# con-left.net
KiCad netlist of a schematic drawn in Altium Designer
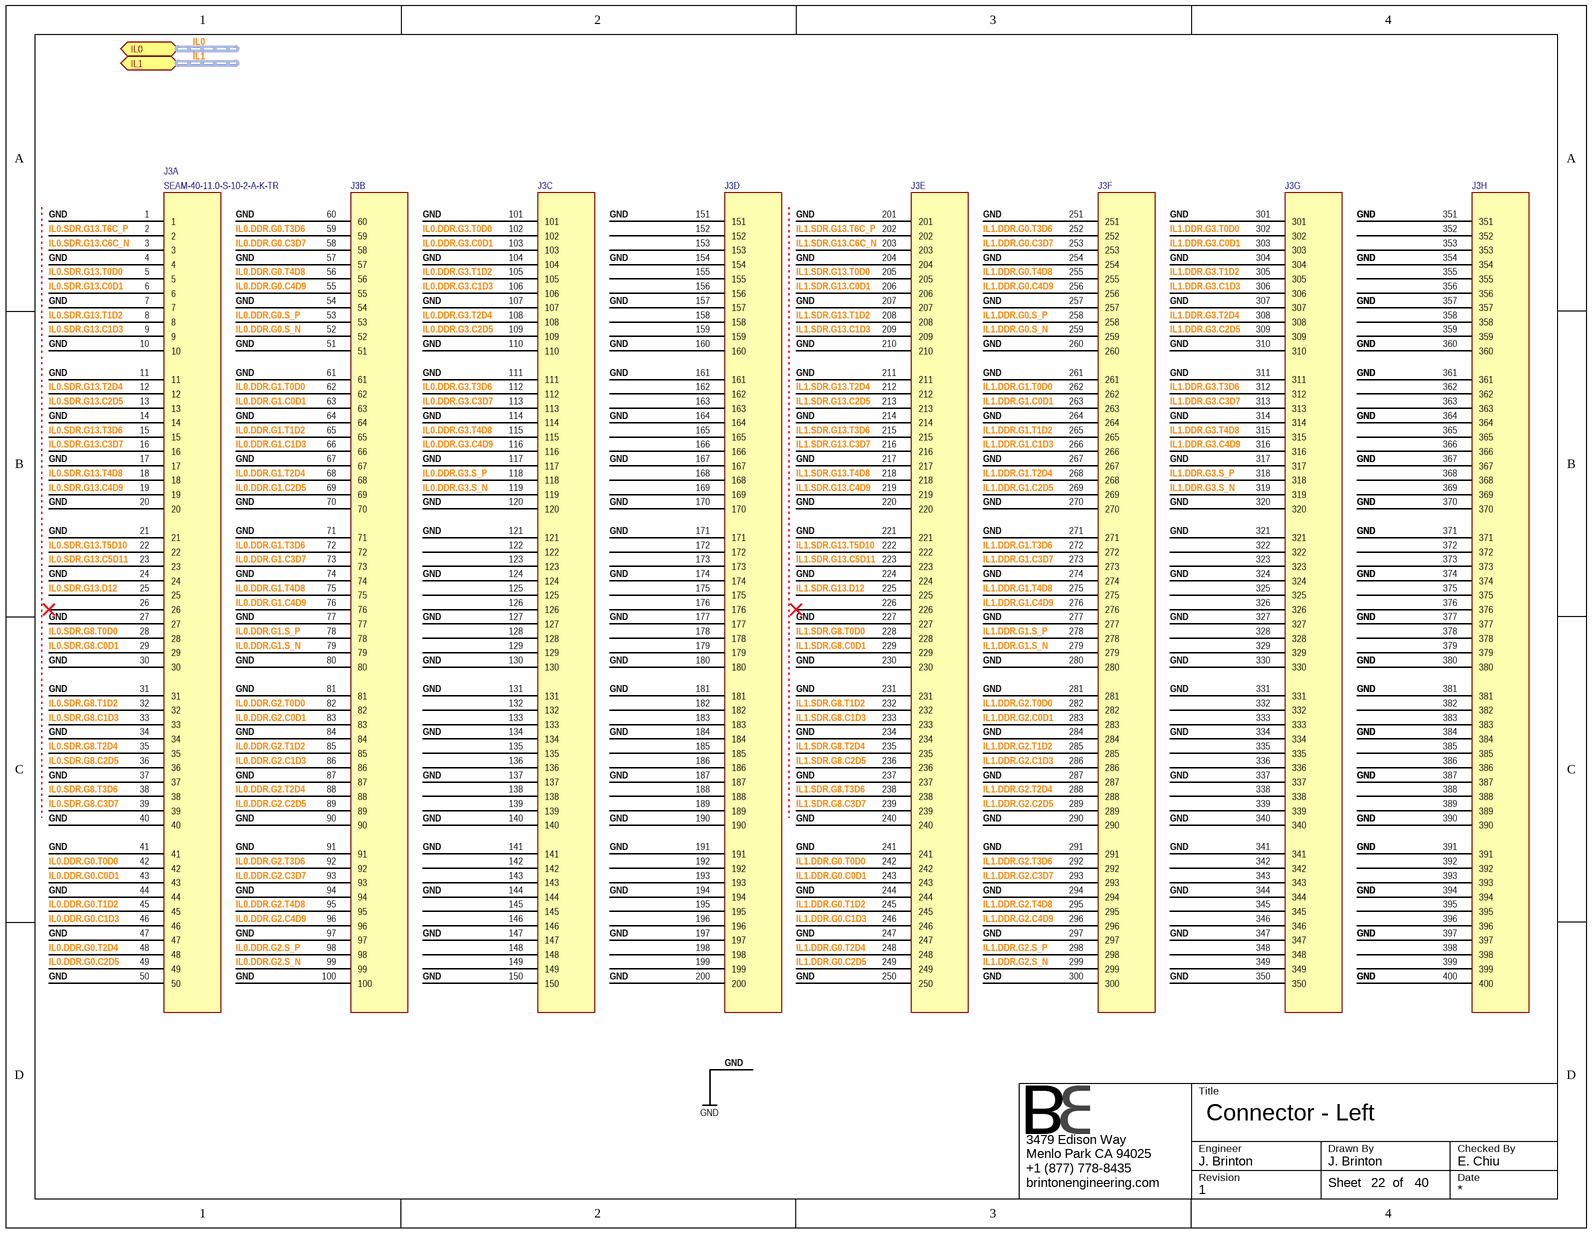
[diagram p0: con-left.SchDoc]

(export (version "E")
  (design (tool "Eeschema 10.0.6"))
  (components
    (comp (ref "J3")
      (value "SEAM-40-11.0-S-10-2-A-K-TR")
      (footprint "samtec:SEAM-40-11.0-S-10-2-A-K-TR")
      (description "Terminal Array Assembly, Surface Mount, 0.050\" Pitch, 400 Pins")
      (fields (field (name "MANUFACTURER") "Samtec"))
      (libsource (lib "samtec") (part "SEAM-40-11.0-S-10-2-A-K-TR"))
    )
  )
  (nets
    (net (code "3") (name "/IL0.DDR.G0.C0D1") (class "Default")
      (node (ref "J3") (pin "43") (pinfunction "43_43") (pintype "passive"))
    )
    (net (code "4") (name "/IL0.DDR.G0.C1D3") (class "Default")
      (node (ref "J3") (pin "46") (pinfunction "46_46") (pintype "passive"))
    )
    (net (code "5") (name "/IL0.DDR.G0.C2D5") (class "Default")
      (node (ref "J3") (pin "49") (pinfunction "49_49") (pintype "passive"))
    )
    (net (code "6") (name "/IL0.DDR.G0.C3D7") (class "Default")
      (node (ref "J3") (pin "58") (pinfunction "58_58") (pintype "passive"))
    )
    (net (code "7") (name "/IL0.DDR.G0.C4D9") (class "Default")
      (node (ref "J3") (pin "55") (pinfunction "55_55") (pintype "passive"))
    )
    (net (code "8") (name "/IL0.DDR.G0.S_N") (class "Default")
      (node (ref "J3") (pin "52") (pinfunction "52_52") (pintype "passive"))
    )
    (net (code "9") (name "/IL0.DDR.G0.S_P") (class "Default")
      (node (ref "J3") (pin "53") (pinfunction "53_53") (pintype "passive"))
    )
    (net (code "10") (name "/IL0.DDR.G0.T0D0") (class "Default")
      (node (ref "J3") (pin "42") (pinfunction "42_42") (pintype "passive"))
    )
    (net (code "11") (name "/IL0.DDR.G0.T1D2") (class "Default")
      (node (ref "J3") (pin "45") (pinfunction "45_45") (pintype "passive"))
    )
    (net (code "12") (name "/IL0.DDR.G0.T2D4") (class "Default")
      (node (ref "J3") (pin "48") (pinfunction "48_48") (pintype "passive"))
    )
    (net (code "13") (name "/IL0.DDR.G0.T3D6") (class "Default")
      (node (ref "J3") (pin "59") (pinfunction "59_59") (pintype "passive"))
    )
    (net (code "14") (name "/IL0.DDR.G0.T4D8") (class "Default")
      (node (ref "J3") (pin "56") (pinfunction "56_56") (pintype "passive"))
    )
    (net (code "15") (name "/IL0.DDR.G1.C0D1") (class "Default")
      (node (ref "J3") (pin "63") (pinfunction "63_63") (pintype "passive"))
    )
    (net (code "16") (name "/IL0.DDR.G1.C1D3") (class "Default")
      (node (ref "J3") (pin "66") (pinfunction "66_66") (pintype "passive"))
    )
    (net (code "17") (name "/IL0.DDR.G1.C2D5") (class "Default")
      (node (ref "J3") (pin "69") (pinfunction "69_69") (pintype "passive"))
    )
    (net (code "18") (name "/IL0.DDR.G1.C3D7") (class "Default")
      (node (ref "J3") (pin "73") (pinfunction "73_73") (pintype "passive"))
    )
    (net (code "19") (name "/IL0.DDR.G1.C4D9") (class "Default")
      (node (ref "J3") (pin "76") (pinfunction "76_76") (pintype "passive"))
    )
    (net (code "20") (name "/IL0.DDR.G1.S_N") (class "Default")
      (node (ref "J3") (pin "79") (pinfunction "79_79") (pintype "passive"))
    )
    (net (code "21") (name "/IL0.DDR.G1.S_P") (class "Default")
      (node (ref "J3") (pin "78") (pinfunction "78_78") (pintype "passive"))
    )
    (net (code "22") (name "/IL0.DDR.G1.T0D0") (class "Default")
      (node (ref "J3") (pin "62") (pinfunction "62_62") (pintype "passive"))
    )
    (net (code "23") (name "/IL0.DDR.G1.T1D2") (class "Default")
      (node (ref "J3") (pin "65") (pinfunction "65_65") (pintype "passive"))
    )
    (net (code "24") (name "/IL0.DDR.G1.T2D4") (class "Default")
      (node (ref "J3") (pin "68") (pinfunction "68_68") (pintype "passive"))
    )
    (net (code "25") (name "/IL0.DDR.G1.T3D6") (class "Default")
      (node (ref "J3") (pin "72") (pinfunction "72_72") (pintype "passive"))
    )
    (net (code "26") (name "/IL0.DDR.G1.T4D8") (class "Default")
      (node (ref "J3") (pin "75") (pinfunction "75_75") (pintype "passive"))
    )
    (net (code "27") (name "/IL0.DDR.G2.C0D1") (class "Default")
      (node (ref "J3") (pin "83") (pinfunction "83_83") (pintype "passive"))
    )
    (net (code "28") (name "/IL0.DDR.G2.C1D3") (class "Default")
      (node (ref "J3") (pin "86") (pinfunction "86_86") (pintype "passive"))
    )
    (net (code "29") (name "/IL0.DDR.G2.C2D5") (class "Default")
      (node (ref "J3") (pin "89") (pinfunction "89_89") (pintype "passive"))
    )
    (net (code "30") (name "/IL0.DDR.G2.C3D7") (class "Default")
      (node (ref "J3") (pin "93") (pinfunction "93_93") (pintype "passive"))
    )
    (net (code "31") (name "/IL0.DDR.G2.C4D9") (class "Default")
      (node (ref "J3") (pin "96") (pinfunction "96_96") (pintype "passive"))
    )
    (net (code "32") (name "/IL0.DDR.G2.S_N") (class "Default")
      (node (ref "J3") (pin "99") (pinfunction "99_99") (pintype "passive"))
    )
    (net (code "33") (name "/IL0.DDR.G2.S_P") (class "Default")
      (node (ref "J3") (pin "98") (pinfunction "98_98") (pintype "passive"))
    )
    (net (code "34") (name "/IL0.DDR.G2.T0D0") (class "Default")
      (node (ref "J3") (pin "82") (pinfunction "82_82") (pintype "passive"))
    )
    (net (code "35") (name "/IL0.DDR.G2.T1D2") (class "Default")
      (node (ref "J3") (pin "85") (pinfunction "85_85") (pintype "passive"))
    )
    (net (code "36") (name "/IL0.DDR.G2.T2D4") (class "Default")
      (node (ref "J3") (pin "88") (pinfunction "88_88") (pintype "passive"))
    )
    (net (code "37") (name "/IL0.DDR.G2.T3D6") (class "Default")
      (node (ref "J3") (pin "92") (pinfunction "92_92") (pintype "passive"))
    )
    (net (code "38") (name "/IL0.DDR.G2.T4D8") (class "Default")
      (node (ref "J3") (pin "95") (pinfunction "95_95") (pintype "passive"))
    )
    (net (code "39") (name "/IL0.DDR.G3.C0D1") (class "Default")
      (node (ref "J3") (pin "103") (pinfunction "103_103") (pintype "passive"))
    )
    (net (code "40") (name "/IL0.DDR.G3.C1D3") (class "Default")
      (node (ref "J3") (pin "106") (pinfunction "106_106") (pintype "passive"))
    )
    (net (code "41") (name "/IL0.DDR.G3.C2D5") (class "Default")
      (node (ref "J3") (pin "109") (pinfunction "109_109") (pintype "passive"))
    )
    (net (code "42") (name "/IL0.DDR.G3.C3D7") (class "Default")
      (node (ref "J3") (pin "113") (pinfunction "113_113") (pintype "passive"))
    )
    (net (code "43") (name "/IL0.DDR.G3.C4D9") (class "Default")
      (node (ref "J3") (pin "116") (pinfunction "116_116") (pintype "passive"))
    )
    (net (code "44") (name "/IL0.DDR.G3.S_N") (class "Default")
      (node (ref "J3") (pin "119") (pinfunction "119_119") (pintype "passive"))
    )
    (net (code "45") (name "/IL0.DDR.G3.S_P") (class "Default")
      (node (ref "J3") (pin "118") (pinfunction "118_118") (pintype "passive"))
    )
    (net (code "46") (name "/IL0.DDR.G3.T0D0") (class "Default")
      (node (ref "J3") (pin "102") (pinfunction "102_102") (pintype "passive"))
    )
    (net (code "47") (name "/IL0.DDR.G3.T1D2") (class "Default")
      (node (ref "J3") (pin "105") (pinfunction "105_105") (pintype "passive"))
    )
    (net (code "48") (name "/IL0.DDR.G3.T2D4") (class "Default")
      (node (ref "J3") (pin "108") (pinfunction "108_108") (pintype "passive"))
    )
    (net (code "49") (name "/IL0.DDR.G3.T3D6") (class "Default")
      (node (ref "J3") (pin "112") (pinfunction "112_112") (pintype "passive"))
    )
    (net (code "50") (name "/IL0.DDR.G3.T4D8") (class "Default")
      (node (ref "J3") (pin "115") (pinfunction "115_115") (pintype "passive"))
    )
    (net (code "51") (name "/IL0.SDR.G8.C0D1") (class "Default")
      (node (ref "J3") (pin "29") (pinfunction "29_29") (pintype "passive"))
    )
    (net (code "52") (name "/IL0.SDR.G8.C1D3") (class "Default")
      (node (ref "J3") (pin "33") (pinfunction "33_33") (pintype "passive"))
    )
    (net (code "53") (name "/IL0.SDR.G8.C2D5") (class "Default")
      (node (ref "J3") (pin "36") (pinfunction "36_36") (pintype "passive"))
    )
    (net (code "54") (name "/IL0.SDR.G8.C3D7") (class "Default")
      (node (ref "J3") (pin "39") (pinfunction "39_39") (pintype "passive"))
    )
    (net (code "55") (name "/IL0.SDR.G8.T0D0") (class "Default")
      (node (ref "J3") (pin "28") (pinfunction "28_28") (pintype "passive"))
    )
    (net (code "56") (name "/IL0.SDR.G8.T1D2") (class "Default")
      (node (ref "J3") (pin "32") (pinfunction "32_32") (pintype "passive"))
    )
    (net (code "57") (name "/IL0.SDR.G8.T2D4") (class "Default")
      (node (ref "J3") (pin "35") (pinfunction "35_35") (pintype "passive"))
    )
    (net (code "58") (name "/IL0.SDR.G8.T3D6") (class "Default")
      (node (ref "J3") (pin "38") (pinfunction "38_38") (pintype "passive"))
    )
    (net (code "59") (name "/IL0.SDR.G13.C0D1") (class "Default")
      (node (ref "J3") (pin "6") (pinfunction "6_6") (pintype "passive"))
    )
    (net (code "60") (name "/IL0.SDR.G13.C1D3") (class "Default")
      (node (ref "J3") (pin "9") (pinfunction "9_9") (pintype "passive"))
    )
    (net (code "61") (name "/IL0.SDR.G13.C2D5") (class "Default")
      (node (ref "J3") (pin "13") (pinfunction "13_13") (pintype "passive"))
    )
    (net (code "62") (name "/IL0.SDR.G13.C3D7") (class "Default")
      (node (ref "J3") (pin "16") (pinfunction "16_16") (pintype "passive"))
    )
    (net (code "63") (name "/IL0.SDR.G13.C4D9") (class "Default")
      (node (ref "J3") (pin "19") (pinfunction "19_19") (pintype "passive"))
    )
    (net (code "64") (name "/IL0.SDR.G13.C5D11") (class "Default")
      (node (ref "J3") (pin "23") (pinfunction "23_23") (pintype "passive"))
    )
    (net (code "65") (name "/IL0.SDR.G13.C6C_N") (class "Default")
      (node (ref "J3") (pin "3") (pinfunction "3_3") (pintype "passive"))
    )
    (net (code "66") (name "/IL0.SDR.G13.D12") (class "Default")
      (node (ref "J3") (pin "25") (pinfunction "25_25") (pintype "passive"))
    )
    (net (code "67") (name "/IL0.SDR.G13.T0D0") (class "Default")
      (node (ref "J3") (pin "5") (pinfunction "5_5") (pintype "passive"))
    )
    (net (code "68") (name "/IL0.SDR.G13.T1D2") (class "Default")
      (node (ref "J3") (pin "8") (pinfunction "8_8") (pintype "passive"))
    )
    (net (code "69") (name "/IL0.SDR.G13.T2D4") (class "Default")
      (node (ref "J3") (pin "12") (pinfunction "12_12") (pintype "passive"))
    )
    (net (code "70") (name "/IL0.SDR.G13.T3D6") (class "Default")
      (node (ref "J3") (pin "15") (pinfunction "15_15") (pintype "passive"))
    )
    (net (code "71") (name "/IL0.SDR.G13.T4D8") (class "Default")
      (node (ref "J3") (pin "18") (pinfunction "18_18") (pintype "passive"))
    )
    (net (code "72") (name "/IL0.SDR.G13.T5D10") (class "Default")
      (node (ref "J3") (pin "22") (pinfunction "22_22") (pintype "passive"))
    )
    (net (code "73") (name "/IL0.SDR.G13.T6C_P") (class "Default")
      (node (ref "J3") (pin "2") (pinfunction "2_2") (pintype "passive"))
    )
    (net (code "74") (name "/IL1.DDR.G0.C0D1") (class "Default")
      (node (ref "J3") (pin "243") (pinfunction "243_243") (pintype "passive"))
    )
    (net (code "75") (name "/IL1.DDR.G0.C1D3") (class "Default")
      (node (ref "J3") (pin "246") (pinfunction "246_246") (pintype "passive"))
    )
    (net (code "76") (name "/IL1.DDR.G0.C2D5") (class "Default")
      (node (ref "J3") (pin "249") (pinfunction "249_249") (pintype "passive"))
    )
    (net (code "77") (name "/IL1.DDR.G0.C3D7") (class "Default")
      (node (ref "J3") (pin "253") (pinfunction "253_253") (pintype "passive"))
    )
    (net (code "78") (name "/IL1.DDR.G0.C4D9") (class "Default")
      (node (ref "J3") (pin "256") (pinfunction "256_256") (pintype "passive"))
    )
    (net (code "79") (name "/IL1.DDR.G0.S_N") (class "Default")
      (node (ref "J3") (pin "259") (pinfunction "259_259") (pintype "passive"))
    )
    (net (code "80") (name "/IL1.DDR.G0.S_P") (class "Default")
      (node (ref "J3") (pin "258") (pinfunction "258_258") (pintype "passive"))
    )
    (net (code "81") (name "/IL1.DDR.G0.T0D0") (class "Default")
      (node (ref "J3") (pin "242") (pinfunction "242_242") (pintype "passive"))
    )
    (net (code "82") (name "/IL1.DDR.G0.T1D2") (class "Default")
      (node (ref "J3") (pin "245") (pinfunction "245_245") (pintype "passive"))
    )
    (net (code "83") (name "/IL1.DDR.G0.T2D4") (class "Default")
      (node (ref "J3") (pin "248") (pinfunction "248_248") (pintype "passive"))
    )
    (net (code "84") (name "/IL1.DDR.G0.T3D6") (class "Default")
      (node (ref "J3") (pin "252") (pinfunction "252_252") (pintype "passive"))
    )
    (net (code "85") (name "/IL1.DDR.G0.T4D8") (class "Default")
      (node (ref "J3") (pin "255") (pinfunction "255_255") (pintype "passive"))
    )
    (net (code "86") (name "/IL1.DDR.G1.C0D1") (class "Default")
      (node (ref "J3") (pin "263") (pinfunction "263_263") (pintype "passive"))
    )
    (net (code "87") (name "/IL1.DDR.G1.C1D3") (class "Default")
      (node (ref "J3") (pin "266") (pinfunction "266_266") (pintype "passive"))
    )
    (net (code "88") (name "/IL1.DDR.G1.C2D5") (class "Default")
      (node (ref "J3") (pin "269") (pinfunction "269_269") (pintype "passive"))
    )
    (net (code "89") (name "/IL1.DDR.G1.C3D7") (class "Default")
      (node (ref "J3") (pin "273") (pinfunction "273_273") (pintype "passive"))
    )
    (net (code "90") (name "/IL1.DDR.G1.C4D9") (class "Default")
      (node (ref "J3") (pin "276") (pinfunction "276_276") (pintype "passive"))
    )
    (net (code "91") (name "/IL1.DDR.G1.S_N") (class "Default")
      (node (ref "J3") (pin "279") (pinfunction "279_279") (pintype "passive"))
    )
    (net (code "92") (name "/IL1.DDR.G1.S_P") (class "Default")
      (node (ref "J3") (pin "278") (pinfunction "278_278") (pintype "passive"))
    )
    (net (code "93") (name "/IL1.DDR.G1.T0D0") (class "Default")
      (node (ref "J3") (pin "262") (pinfunction "262_262") (pintype "passive"))
    )
    (net (code "94") (name "/IL1.DDR.G1.T1D2") (class "Default")
      (node (ref "J3") (pin "265") (pinfunction "265_265") (pintype "passive"))
    )
    (net (code "95") (name "/IL1.DDR.G1.T2D4") (class "Default")
      (node (ref "J3") (pin "268") (pinfunction "268_268") (pintype "passive"))
    )
    (net (code "96") (name "/IL1.DDR.G1.T3D6") (class "Default")
      (node (ref "J3") (pin "272") (pinfunction "272_272") (pintype "passive"))
    )
    (net (code "97") (name "/IL1.DDR.G1.T4D8") (class "Default")
      (node (ref "J3") (pin "275") (pinfunction "275_275") (pintype "passive"))
    )
    (net (code "98") (name "/IL1.DDR.G2.C0D1") (class "Default")
      (node (ref "J3") (pin "283") (pinfunction "283_283") (pintype "passive"))
    )
    (net (code "99") (name "/IL1.DDR.G2.C1D3") (class "Default")
      (node (ref "J3") (pin "286") (pinfunction "286_286") (pintype "passive"))
    )
    (net (code "100") (name "/IL1.DDR.G2.C2D5") (class "Default")
      (node (ref "J3") (pin "289") (pinfunction "289_289") (pintype "passive"))
    )
    (net (code "101") (name "/IL1.DDR.G2.C3D7") (class "Default")
      (node (ref "J3") (pin "293") (pinfunction "293_293") (pintype "passive"))
    )
    (net (code "102") (name "/IL1.DDR.G2.C4D9") (class "Default")
      (node (ref "J3") (pin "296") (pinfunction "296_296") (pintype "passive"))
    )
    (net (code "103") (name "/IL1.DDR.G2.S_N") (class "Default")
      (node (ref "J3") (pin "299") (pinfunction "299_299") (pintype "passive"))
    )
    (net (code "104") (name "/IL1.DDR.G2.S_P") (class "Default")
      (node (ref "J3") (pin "298") (pinfunction "298_298") (pintype "passive"))
    )
    (net (code "105") (name "/IL1.DDR.G2.T0D0") (class "Default")
      (node (ref "J3") (pin "282") (pinfunction "282_282") (pintype "passive"))
    )
    (net (code "106") (name "/IL1.DDR.G2.T1D2") (class "Default")
      (node (ref "J3") (pin "285") (pinfunction "285_285") (pintype "passive"))
    )
    (net (code "107") (name "/IL1.DDR.G2.T2D4") (class "Default")
      (node (ref "J3") (pin "288") (pinfunction "288_288") (pintype "passive"))
    )
    (net (code "108") (name "/IL1.DDR.G2.T3D6") (class "Default")
      (node (ref "J3") (pin "292") (pinfunction "292_292") (pintype "passive"))
    )
    (net (code "109") (name "/IL1.DDR.G2.T4D8") (class "Default")
      (node (ref "J3") (pin "295") (pinfunction "295_295") (pintype "passive"))
    )
    (net (code "110") (name "/IL1.DDR.G3.C0D1") (class "Default")
      (node (ref "J3") (pin "303") (pinfunction "303_303") (pintype "passive"))
    )
    (net (code "111") (name "/IL1.DDR.G3.C1D3") (class "Default")
      (node (ref "J3") (pin "306") (pinfunction "306_306") (pintype "passive"))
    )
    (net (code "112") (name "/IL1.DDR.G3.C2D5") (class "Default")
      (node (ref "J3") (pin "309") (pinfunction "309_309") (pintype "passive"))
    )
    (net (code "113") (name "/IL1.DDR.G3.C3D7") (class "Default")
      (node (ref "J3") (pin "313") (pinfunction "313_313") (pintype "passive"))
    )
    (net (code "114") (name "/IL1.DDR.G3.C4D9") (class "Default")
      (node (ref "J3") (pin "316") (pinfunction "316_316") (pintype "passive"))
    )
    (net (code "115") (name "/IL1.DDR.G3.S_N") (class "Default")
      (node (ref "J3") (pin "319") (pinfunction "319_319") (pintype "passive"))
    )
    (net (code "116") (name "/IL1.DDR.G3.S_P") (class "Default")
      (node (ref "J3") (pin "318") (pinfunction "318_318") (pintype "passive"))
    )
    (net (code "117") (name "/IL1.DDR.G3.T0D0") (class "Default")
      (node (ref "J3") (pin "302") (pinfunction "302_302") (pintype "passive"))
    )
    (net (code "118") (name "/IL1.DDR.G3.T1D2") (class "Default")
      (node (ref "J3") (pin "305") (pinfunction "305_305") (pintype "passive"))
    )
    (net (code "119") (name "/IL1.DDR.G3.T2D4") (class "Default")
      (node (ref "J3") (pin "308") (pinfunction "308_308") (pintype "passive"))
    )
    (net (code "120") (name "/IL1.DDR.G3.T3D6") (class "Default")
      (node (ref "J3") (pin "312") (pinfunction "312_312") (pintype "passive"))
    )
    (net (code "121") (name "/IL1.DDR.G3.T4D8") (class "Default")
      (node (ref "J3") (pin "315") (pinfunction "315_315") (pintype "passive"))
    )
    (net (code "122") (name "/IL1.SDR.G8.C0D1") (class "Default")
      (node (ref "J3") (pin "229") (pinfunction "229_229") (pintype "passive"))
    )
    (net (code "123") (name "/IL1.SDR.G8.C1D3") (class "Default")
      (node (ref "J3") (pin "233") (pinfunction "233_233") (pintype "passive"))
    )
    (net (code "124") (name "/IL1.SDR.G8.C2D5") (class "Default")
      (node (ref "J3") (pin "236") (pinfunction "236_236") (pintype "passive"))
    )
    (net (code "125") (name "/IL1.SDR.G8.C3D7") (class "Default")
      (node (ref "J3") (pin "239") (pinfunction "239_239") (pintype "passive"))
    )
    (net (code "126") (name "/IL1.SDR.G8.T0D0") (class "Default")
      (node (ref "J3") (pin "228") (pinfunction "228_228") (pintype "passive"))
    )
    (net (code "127") (name "/IL1.SDR.G8.T1D2") (class "Default")
      (node (ref "J3") (pin "232") (pinfunction "232_232") (pintype "passive"))
    )
    (net (code "128") (name "/IL1.SDR.G8.T2D4") (class "Default")
      (node (ref "J3") (pin "235") (pinfunction "235_235") (pintype "passive"))
    )
    (net (code "129") (name "/IL1.SDR.G8.T3D6") (class "Default")
      (node (ref "J3") (pin "238") (pinfunction "238_238") (pintype "passive"))
    )
    (net (code "130") (name "/IL1.SDR.G13.C0D1") (class "Default")
      (node (ref "J3") (pin "206") (pinfunction "206_206") (pintype "passive"))
    )
    (net (code "131") (name "/IL1.SDR.G13.C1D3") (class "Default")
      (node (ref "J3") (pin "209") (pinfunction "209_209") (pintype "passive"))
    )
    (net (code "132") (name "/IL1.SDR.G13.C2D5") (class "Default")
      (node (ref "J3") (pin "213") (pinfunction "213_213") (pintype "passive"))
    )
    (net (code "133") (name "/IL1.SDR.G13.C3D7") (class "Default")
      (node (ref "J3") (pin "216") (pinfunction "216_216") (pintype "passive"))
    )
    (net (code "134") (name "/IL1.SDR.G13.C4D9") (class "Default")
      (node (ref "J3") (pin "219") (pinfunction "219_219") (pintype "passive"))
    )
    (net (code "135") (name "/IL1.SDR.G13.C5D11") (class "Default")
      (node (ref "J3") (pin "223") (pinfunction "223_223") (pintype "passive"))
    )
    (net (code "136") (name "/IL1.SDR.G13.C6C_N") (class "Default")
      (node (ref "J3") (pin "203") (pinfunction "203_203") (pintype "passive"))
    )
    (net (code "137") (name "/IL1.SDR.G13.D12") (class "Default")
      (node (ref "J3") (pin "225") (pinfunction "225_225") (pintype "passive"))
    )
    (net (code "138") (name "/IL1.SDR.G13.T0D0") (class "Default")
      (node (ref "J3") (pin "205") (pinfunction "205_205") (pintype "passive"))
    )
    (net (code "139") (name "/IL1.SDR.G13.T1D2") (class "Default")
      (node (ref "J3") (pin "208") (pinfunction "208_208") (pintype "passive"))
    )
    (net (code "140") (name "/IL1.SDR.G13.T2D4") (class "Default")
      (node (ref "J3") (pin "212") (pinfunction "212_212") (pintype "passive"))
    )
    (net (code "141") (name "/IL1.SDR.G13.T3D6") (class "Default")
      (node (ref "J3") (pin "215") (pinfunction "215_215") (pintype "passive"))
    )
    (net (code "142") (name "/IL1.SDR.G13.T4D8") (class "Default")
      (node (ref "J3") (pin "218") (pinfunction "218_218") (pintype "passive"))
    )
    (net (code "143") (name "/IL1.SDR.G13.T5D10") (class "Default")
      (node (ref "J3") (pin "222") (pinfunction "222_222") (pintype "passive"))
    )
    (net (code "144") (name "/IL1.SDR.G13.T6C_P") (class "Default")
      (node (ref "J3") (pin "202") (pinfunction "202_202") (pintype "passive"))
    )
    (net (code "147") (name "GND") (class "Default")
      (node (ref "J3") (pin "1") (pinfunction "1_1") (pintype "passive"))
      (node (ref "J3") (pin "10") (pinfunction "10_10") (pintype "passive"))
      (node (ref "J3") (pin "100") (pinfunction "100_100") (pintype "passive"))
      (node (ref "J3") (pin "101") (pinfunction "101_101") (pintype "passive"))
      (node (ref "J3") (pin "104") (pinfunction "104_104") (pintype "passive"))
      (node (ref "J3") (pin "107") (pinfunction "107_107") (pintype "passive"))
      (node (ref "J3") (pin "11") (pinfunction "11_11") (pintype "passive"))
      (node (ref "J3") (pin "110") (pinfunction "110_110") (pintype "passive"))
      (node (ref "J3") (pin "111") (pinfunction "111_111") (pintype "passive"))
      (node (ref "J3") (pin "114") (pinfunction "114_114") (pintype "passive"))
      (node (ref "J3") (pin "117") (pinfunction "117_117") (pintype "passive"))
      (node (ref "J3") (pin "120") (pinfunction "120_120") (pintype "passive"))
      (node (ref "J3") (pin "121") (pinfunction "121_121") (pintype "passive"))
      (node (ref "J3") (pin "124") (pinfunction "124_124") (pintype "passive"))
      (node (ref "J3") (pin "127") (pinfunction "127_127") (pintype "passive"))
      (node (ref "J3") (pin "130") (pinfunction "130_130") (pintype "passive"))
      (node (ref "J3") (pin "131") (pinfunction "131_131") (pintype "passive"))
      (node (ref "J3") (pin "134") (pinfunction "134_134") (pintype "passive"))
      (node (ref "J3") (pin "137") (pinfunction "137_137") (pintype "passive"))
      (node (ref "J3") (pin "14") (pinfunction "14_14") (pintype "passive"))
      (node (ref "J3") (pin "140") (pinfunction "140_140") (pintype "passive"))
      (node (ref "J3") (pin "141") (pinfunction "141_141") (pintype "passive"))
      (node (ref "J3") (pin "144") (pinfunction "144_144") (pintype "passive"))
      (node (ref "J3") (pin "147") (pinfunction "147_147") (pintype "passive"))
      (node (ref "J3") (pin "150") (pinfunction "150_150") (pintype "passive"))
      (node (ref "J3") (pin "151") (pinfunction "151_151") (pintype "passive"))
      (node (ref "J3") (pin "154") (pinfunction "154_154") (pintype "passive"))
      (node (ref "J3") (pin "157") (pinfunction "157_157") (pintype "passive"))
      (node (ref "J3") (pin "160") (pinfunction "160_160") (pintype "passive"))
      (node (ref "J3") (pin "161") (pinfunction "161_161") (pintype "passive"))
      (node (ref "J3") (pin "164") (pinfunction "164_164") (pintype "passive"))
      (node (ref "J3") (pin "167") (pinfunction "167_167") (pintype "passive"))
      (node (ref "J3") (pin "17") (pinfunction "17_17") (pintype "passive"))
      (node (ref "J3") (pin "170") (pinfunction "170_170") (pintype "passive"))
      (node (ref "J3") (pin "171") (pinfunction "171_171") (pintype "passive"))
      (node (ref "J3") (pin "174") (pinfunction "174_174") (pintype "passive"))
      (node (ref "J3") (pin "177") (pinfunction "177_177") (pintype "passive"))
      (node (ref "J3") (pin "180") (pinfunction "180_180") (pintype "passive"))
      (node (ref "J3") (pin "181") (pinfunction "181_181") (pintype "passive"))
      (node (ref "J3") (pin "184") (pinfunction "184_184") (pintype "passive"))
      (node (ref "J3") (pin "187") (pinfunction "187_187") (pintype "passive"))
      (node (ref "J3") (pin "190") (pinfunction "190_190") (pintype "passive"))
      (node (ref "J3") (pin "191") (pinfunction "191_191") (pintype "passive"))
      (node (ref "J3") (pin "194") (pinfunction "194_194") (pintype "passive"))
      (node (ref "J3") (pin "197") (pinfunction "197_197") (pintype "passive"))
      (node (ref "J3") (pin "20") (pinfunction "20_20") (pintype "passive"))
      (node (ref "J3") (pin "200") (pinfunction "200_200") (pintype "passive"))
      (node (ref "J3") (pin "201") (pinfunction "201_201") (pintype "passive"))
      (node (ref "J3") (pin "204") (pinfunction "204_204") (pintype "passive"))
      (node (ref "J3") (pin "207") (pinfunction "207_207") (pintype "passive"))
      (node (ref "J3") (pin "21") (pinfunction "21_21") (pintype "passive"))
      (node (ref "J3") (pin "210") (pinfunction "210_210") (pintype "passive"))
      (node (ref "J3") (pin "211") (pinfunction "211_211") (pintype "passive"))
      (node (ref "J3") (pin "214") (pinfunction "214_214") (pintype "passive"))
      (node (ref "J3") (pin "217") (pinfunction "217_217") (pintype "passive"))
      (node (ref "J3") (pin "220") (pinfunction "220_220") (pintype "passive"))
      (node (ref "J3") (pin "221") (pinfunction "221_221") (pintype "passive"))
      (node (ref "J3") (pin "224") (pinfunction "224_224") (pintype "passive"))
      (node (ref "J3") (pin "227") (pinfunction "227_227") (pintype "passive"))
      (node (ref "J3") (pin "230") (pinfunction "230_230") (pintype "passive"))
      (node (ref "J3") (pin "231") (pinfunction "231_231") (pintype "passive"))
      (node (ref "J3") (pin "234") (pinfunction "234_234") (pintype "passive"))
      (node (ref "J3") (pin "237") (pinfunction "237_237") (pintype "passive"))
      (node (ref "J3") (pin "24") (pinfunction "24_24") (pintype "passive"))
      (node (ref "J3") (pin "240") (pinfunction "240_240") (pintype "passive"))
      (node (ref "J3") (pin "241") (pinfunction "241_241") (pintype "passive"))
      (node (ref "J3") (pin "244") (pinfunction "244_244") (pintype "passive"))
      (node (ref "J3") (pin "247") (pinfunction "247_247") (pintype "passive"))
      (node (ref "J3") (pin "250") (pinfunction "250_250") (pintype "passive"))
      (node (ref "J3") (pin "251") (pinfunction "251_251") (pintype "passive"))
      (node (ref "J3") (pin "254") (pinfunction "254_254") (pintype "passive"))
      (node (ref "J3") (pin "257") (pinfunction "257_257") (pintype "passive"))
      (node (ref "J3") (pin "260") (pinfunction "260_260") (pintype "passive"))
      (node (ref "J3") (pin "261") (pinfunction "261_261") (pintype "passive"))
      (node (ref "J3") (pin "264") (pinfunction "264_264") (pintype "passive"))
      (node (ref "J3") (pin "267") (pinfunction "267_267") (pintype "passive"))
      (node (ref "J3") (pin "27") (pinfunction "27_27") (pintype "passive"))
      (node (ref "J3") (pin "270") (pinfunction "270_270") (pintype "passive"))
      (node (ref "J3") (pin "271") (pinfunction "271_271") (pintype "passive"))
      (node (ref "J3") (pin "274") (pinfunction "274_274") (pintype "passive"))
      (node (ref "J3") (pin "277") (pinfunction "277_277") (pintype "passive"))
      (node (ref "J3") (pin "280") (pinfunction "280_280") (pintype "passive"))
      (node (ref "J3") (pin "281") (pinfunction "281_281") (pintype "passive"))
      (node (ref "J3") (pin "284") (pinfunction "284_284") (pintype "passive"))
      (node (ref "J3") (pin "287") (pinfunction "287_287") (pintype "passive"))
      (node (ref "J3") (pin "290") (pinfunction "290_290") (pintype "passive"))
      (node (ref "J3") (pin "291") (pinfunction "291_291") (pintype "passive"))
      (node (ref "J3") (pin "294") (pinfunction "294_294") (pintype "passive"))
      (node (ref "J3") (pin "297") (pinfunction "297_297") (pintype "passive"))
      (node (ref "J3") (pin "30") (pinfunction "30_30") (pintype "passive"))
      (node (ref "J3") (pin "300") (pinfunction "300_300") (pintype "passive"))
      (node (ref "J3") (pin "301") (pinfunction "301_301") (pintype "passive"))
      (node (ref "J3") (pin "304") (pinfunction "304_304") (pintype "passive"))
      (node (ref "J3") (pin "307") (pinfunction "307_307") (pintype "passive"))
      (node (ref "J3") (pin "31") (pinfunction "31_31") (pintype "passive"))
      (node (ref "J3") (pin "310") (pinfunction "310_310") (pintype "passive"))
      (node (ref "J3") (pin "311") (pinfunction "311_311") (pintype "passive"))
      (node (ref "J3") (pin "314") (pinfunction "314_314") (pintype "passive"))
      (node (ref "J3") (pin "317") (pinfunction "317_317") (pintype "passive"))
      (node (ref "J3") (pin "320") (pinfunction "320_320") (pintype "passive"))
      (node (ref "J3") (pin "321") (pinfunction "321_321") (pintype "passive"))
      (node (ref "J3") (pin "324") (pinfunction "324_324") (pintype "passive"))
      (node (ref "J3") (pin "327") (pinfunction "327_327") (pintype "passive"))
      (node (ref "J3") (pin "330") (pinfunction "330_330") (pintype "passive"))
      (node (ref "J3") (pin "331") (pinfunction "331_331") (pintype "passive"))
      (node (ref "J3") (pin "334") (pinfunction "334_334") (pintype "passive"))
      (node (ref "J3") (pin "337") (pinfunction "337_337") (pintype "passive"))
      (node (ref "J3") (pin "34") (pinfunction "34_34") (pintype "passive"))
      (node (ref "J3") (pin "340") (pinfunction "340_340") (pintype "passive"))
      (node (ref "J3") (pin "341") (pinfunction "341_341") (pintype "passive"))
      (node (ref "J3") (pin "344") (pinfunction "344_344") (pintype "passive"))
      (node (ref "J3") (pin "347") (pinfunction "347_347") (pintype "passive"))
      (node (ref "J3") (pin "350") (pinfunction "350_350") (pintype "passive"))
      (node (ref "J3") (pin "351") (pinfunction "351_351") (pintype "passive"))
      (node (ref "J3") (pin "354") (pinfunction "354_354") (pintype "passive"))
      (node (ref "J3") (pin "357") (pinfunction "357_357") (pintype "passive"))
      (node (ref "J3") (pin "360") (pinfunction "360_360") (pintype "passive"))
      (node (ref "J3") (pin "361") (pinfunction "361_361") (pintype "passive"))
      (node (ref "J3") (pin "364") (pinfunction "364_364") (pintype "passive"))
      (node (ref "J3") (pin "367") (pinfunction "367_367") (pintype "passive"))
      (node (ref "J3") (pin "37") (pinfunction "37_37") (pintype "passive"))
      (node (ref "J3") (pin "370") (pinfunction "370_370") (pintype "passive"))
      (node (ref "J3") (pin "371") (pinfunction "371_371") (pintype "passive"))
      (node (ref "J3") (pin "374") (pinfunction "374_374") (pintype "passive"))
      (node (ref "J3") (pin "377") (pinfunction "377_377") (pintype "passive"))
      (node (ref "J3") (pin "380") (pinfunction "380_380") (pintype "passive"))
      (node (ref "J3") (pin "381") (pinfunction "381_381") (pintype "passive"))
      (node (ref "J3") (pin "384") (pinfunction "384_384") (pintype "passive"))
      (node (ref "J3") (pin "387") (pinfunction "387_387") (pintype "passive"))
      (node (ref "J3") (pin "390") (pinfunction "390_390") (pintype "passive"))
      (node (ref "J3") (pin "391") (pinfunction "391_391") (pintype "passive"))
      (node (ref "J3") (pin "394") (pinfunction "394_394") (pintype "passive"))
      (node (ref "J3") (pin "397") (pinfunction "397_397") (pintype "passive"))
      (node (ref "J3") (pin "4") (pinfunction "4_4") (pintype "passive"))
      (node (ref "J3") (pin "40") (pinfunction "40_40") (pintype "passive"))
      (node (ref "J3") (pin "400") (pinfunction "400_400") (pintype "passive"))
      (node (ref "J3") (pin "41") (pinfunction "41_41") (pintype "passive"))
      (node (ref "J3") (pin "44") (pinfunction "44_44") (pintype "passive"))
      (node (ref "J3") (pin "47") (pinfunction "47_47") (pintype "passive"))
      (node (ref "J3") (pin "50") (pinfunction "50_50") (pintype "passive"))
      (node (ref "J3") (pin "51") (pinfunction "51_51") (pintype "passive"))
      (node (ref "J3") (pin "54") (pinfunction "54_54") (pintype "passive"))
      (node (ref "J3") (pin "57") (pinfunction "57_57") (pintype "passive"))
      (node (ref "J3") (pin "60") (pinfunction "60_60") (pintype "passive"))
      (node (ref "J3") (pin "61") (pinfunction "61_61") (pintype "passive"))
      (node (ref "J3") (pin "64") (pinfunction "64_64") (pintype "passive"))
      (node (ref "J3") (pin "67") (pinfunction "67_67") (pintype "passive"))
      (node (ref "J3") (pin "7") (pinfunction "7_7") (pintype "passive"))
      (node (ref "J3") (pin "70") (pinfunction "70_70") (pintype "passive"))
      (node (ref "J3") (pin "71") (pinfunction "71_71") (pintype "passive"))
      (node (ref "J3") (pin "74") (pinfunction "74_74") (pintype "passive"))
      (node (ref "J3") (pin "77") (pinfunction "77_77") (pintype "passive"))
      (node (ref "J3") (pin "80") (pinfunction "80_80") (pintype "passive"))
      (node (ref "J3") (pin "81") (pinfunction "81_81") (pintype "passive"))
      (node (ref "J3") (pin "84") (pinfunction "84_84") (pintype "passive"))
      (node (ref "J3") (pin "87") (pinfunction "87_87") (pintype "passive"))
      (node (ref "J3") (pin "90") (pinfunction "90_90") (pintype "passive"))
      (node (ref "J3") (pin "91") (pinfunction "91_91") (pintype "passive"))
      (node (ref "J3") (pin "94") (pinfunction "94_94") (pintype "passive"))
      (node (ref "J3") (pin "97") (pinfunction "97_97") (pintype "passive"))
    )
    (net (code "148") (name "unconnected-(J3-Pad26)") (class "Default")
      (node (ref "J3") (pin "26") (pinfunction "26_26") (pintype "passive+no_connect"))
    )
    (net (code "149") (name "unconnected-(J3-Pad122)") (class "Default")
      (node (ref "J3") (pin "122") (pinfunction "122_122") (pintype "passive"))
    )
    (net (code "150") (name "unconnected-(J3-Pad123)") (class "Default")
      (node (ref "J3") (pin "123") (pinfunction "123_123") (pintype "passive"))
    )
    (net (code "151") (name "unconnected-(J3-Pad125)") (class "Default")
      (node (ref "J3") (pin "125") (pinfunction "125_125") (pintype "passive"))
    )
    (net (code "152") (name "unconnected-(J3-Pad126)") (class "Default")
      (node (ref "J3") (pin "126") (pinfunction "126_126") (pintype "passive"))
    )
    (net (code "153") (name "unconnected-(J3-Pad128)") (class "Default")
      (node (ref "J3") (pin "128") (pinfunction "128_128") (pintype "passive"))
    )
    (net (code "154") (name "unconnected-(J3-Pad129)") (class "Default")
      (node (ref "J3") (pin "129") (pinfunction "129_129") (pintype "passive"))
    )
    (net (code "155") (name "unconnected-(J3-Pad132)") (class "Default")
      (node (ref "J3") (pin "132") (pinfunction "132_132") (pintype "passive"))
    )
    (net (code "156") (name "unconnected-(J3-Pad133)") (class "Default")
      (node (ref "J3") (pin "133") (pinfunction "133_133") (pintype "passive"))
    )
    (net (code "157") (name "unconnected-(J3-Pad135)") (class "Default")
      (node (ref "J3") (pin "135") (pinfunction "135_135") (pintype "passive"))
    )
    (net (code "158") (name "unconnected-(J3-Pad136)") (class "Default")
      (node (ref "J3") (pin "136") (pinfunction "136_136") (pintype "passive"))
    )
    (net (code "159") (name "unconnected-(J3-Pad138)") (class "Default")
      (node (ref "J3") (pin "138") (pinfunction "138_138") (pintype "passive"))
    )
    (net (code "160") (name "unconnected-(J3-Pad139)") (class "Default")
      (node (ref "J3") (pin "139") (pinfunction "139_139") (pintype "passive"))
    )
    (net (code "161") (name "unconnected-(J3-Pad142)") (class "Default")
      (node (ref "J3") (pin "142") (pinfunction "142_142") (pintype "passive"))
    )
    (net (code "162") (name "unconnected-(J3-Pad143)") (class "Default")
      (node (ref "J3") (pin "143") (pinfunction "143_143") (pintype "passive"))
    )
    (net (code "163") (name "unconnected-(J3-Pad145)") (class "Default")
      (node (ref "J3") (pin "145") (pinfunction "145_145") (pintype "passive"))
    )
    (net (code "164") (name "unconnected-(J3-Pad146)") (class "Default")
      (node (ref "J3") (pin "146") (pinfunction "146_146") (pintype "passive"))
    )
    (net (code "165") (name "unconnected-(J3-Pad148)") (class "Default")
      (node (ref "J3") (pin "148") (pinfunction "148_148") (pintype "passive"))
    )
    (net (code "166") (name "unconnected-(J3-Pad149)") (class "Default")
      (node (ref "J3") (pin "149") (pinfunction "149_149") (pintype "passive"))
    )
    (net (code "167") (name "unconnected-(J3-Pad152)") (class "Default")
      (node (ref "J3") (pin "152") (pinfunction "152_152") (pintype "passive"))
    )
    (net (code "168") (name "unconnected-(J3-Pad153)") (class "Default")
      (node (ref "J3") (pin "153") (pinfunction "153_153") (pintype "passive"))
    )
    (net (code "169") (name "unconnected-(J3-Pad155)") (class "Default")
      (node (ref "J3") (pin "155") (pinfunction "155_155") (pintype "passive"))
    )
    (net (code "170") (name "unconnected-(J3-Pad156)") (class "Default")
      (node (ref "J3") (pin "156") (pinfunction "156_156") (pintype "passive"))
    )
    (net (code "171") (name "unconnected-(J3-Pad158)") (class "Default")
      (node (ref "J3") (pin "158") (pinfunction "158_158") (pintype "passive"))
    )
    (net (code "172") (name "unconnected-(J3-Pad159)") (class "Default")
      (node (ref "J3") (pin "159") (pinfunction "159_159") (pintype "passive"))
    )
    (net (code "173") (name "unconnected-(J3-Pad162)") (class "Default")
      (node (ref "J3") (pin "162") (pinfunction "162_162") (pintype "passive"))
    )
    (net (code "174") (name "unconnected-(J3-Pad163)") (class "Default")
      (node (ref "J3") (pin "163") (pinfunction "163_163") (pintype "passive"))
    )
    (net (code "175") (name "unconnected-(J3-Pad165)") (class "Default")
      (node (ref "J3") (pin "165") (pinfunction "165_165") (pintype "passive"))
    )
    (net (code "176") (name "unconnected-(J3-Pad166)") (class "Default")
      (node (ref "J3") (pin "166") (pinfunction "166_166") (pintype "passive"))
    )
    (net (code "177") (name "unconnected-(J3-Pad168)") (class "Default")
      (node (ref "J3") (pin "168") (pinfunction "168_168") (pintype "passive"))
    )
    (net (code "178") (name "unconnected-(J3-Pad169)") (class "Default")
      (node (ref "J3") (pin "169") (pinfunction "169_169") (pintype "passive"))
    )
    (net (code "179") (name "unconnected-(J3-Pad172)") (class "Default")
      (node (ref "J3") (pin "172") (pinfunction "172_172") (pintype "passive"))
    )
    (net (code "180") (name "unconnected-(J3-Pad173)") (class "Default")
      (node (ref "J3") (pin "173") (pinfunction "173_173") (pintype "passive"))
    )
    (net (code "181") (name "unconnected-(J3-Pad175)") (class "Default")
      (node (ref "J3") (pin "175") (pinfunction "175_175") (pintype "passive"))
    )
    (net (code "182") (name "unconnected-(J3-Pad176)") (class "Default")
      (node (ref "J3") (pin "176") (pinfunction "176_176") (pintype "passive"))
    )
    (net (code "183") (name "unconnected-(J3-Pad178)") (class "Default")
      (node (ref "J3") (pin "178") (pinfunction "178_178") (pintype "passive"))
    )
    (net (code "184") (name "unconnected-(J3-Pad179)") (class "Default")
      (node (ref "J3") (pin "179") (pinfunction "179_179") (pintype "passive"))
    )
    (net (code "185") (name "unconnected-(J3-Pad182)") (class "Default")
      (node (ref "J3") (pin "182") (pinfunction "182_182") (pintype "passive"))
    )
    (net (code "186") (name "unconnected-(J3-Pad183)") (class "Default")
      (node (ref "J3") (pin "183") (pinfunction "183_183") (pintype "passive"))
    )
    (net (code "187") (name "unconnected-(J3-Pad185)") (class "Default")
      (node (ref "J3") (pin "185") (pinfunction "185_185") (pintype "passive"))
    )
    (net (code "188") (name "unconnected-(J3-Pad186)") (class "Default")
      (node (ref "J3") (pin "186") (pinfunction "186_186") (pintype "passive"))
    )
    (net (code "189") (name "unconnected-(J3-Pad188)") (class "Default")
      (node (ref "J3") (pin "188") (pinfunction "188_188") (pintype "passive"))
    )
    (net (code "190") (name "unconnected-(J3-Pad189)") (class "Default")
      (node (ref "J3") (pin "189") (pinfunction "189_189") (pintype "passive"))
    )
    (net (code "191") (name "unconnected-(J3-Pad192)") (class "Default")
      (node (ref "J3") (pin "192") (pinfunction "192_192") (pintype "passive"))
    )
    (net (code "192") (name "unconnected-(J3-Pad193)") (class "Default")
      (node (ref "J3") (pin "193") (pinfunction "193_193") (pintype "passive"))
    )
    (net (code "193") (name "unconnected-(J3-Pad195)") (class "Default")
      (node (ref "J3") (pin "195") (pinfunction "195_195") (pintype "passive"))
    )
    (net (code "194") (name "unconnected-(J3-Pad196)") (class "Default")
      (node (ref "J3") (pin "196") (pinfunction "196_196") (pintype "passive"))
    )
    (net (code "195") (name "unconnected-(J3-Pad198)") (class "Default")
      (node (ref "J3") (pin "198") (pinfunction "198_198") (pintype "passive"))
    )
    (net (code "196") (name "unconnected-(J3-Pad199)") (class "Default")
      (node (ref "J3") (pin "199") (pinfunction "199_199") (pintype "passive"))
    )
    (net (code "197") (name "unconnected-(J3-Pad226)") (class "Default")
      (node (ref "J3") (pin "226") (pinfunction "226_226") (pintype "passive+no_connect"))
    )
    (net (code "198") (name "unconnected-(J3-Pad322)") (class "Default")
      (node (ref "J3") (pin "322") (pinfunction "322_322") (pintype "passive"))
    )
    (net (code "199") (name "unconnected-(J3-Pad323)") (class "Default")
      (node (ref "J3") (pin "323") (pinfunction "323_323") (pintype "passive"))
    )
    (net (code "200") (name "unconnected-(J3-Pad325)") (class "Default")
      (node (ref "J3") (pin "325") (pinfunction "325_325") (pintype "passive"))
    )
    (net (code "201") (name "unconnected-(J3-Pad326)") (class "Default")
      (node (ref "J3") (pin "326") (pinfunction "326_326") (pintype "passive"))
    )
    (net (code "202") (name "unconnected-(J3-Pad328)") (class "Default")
      (node (ref "J3") (pin "328") (pinfunction "328_328") (pintype "passive"))
    )
    (net (code "203") (name "unconnected-(J3-Pad329)") (class "Default")
      (node (ref "J3") (pin "329") (pinfunction "329_329") (pintype "passive"))
    )
    (net (code "204") (name "unconnected-(J3-Pad332)") (class "Default")
      (node (ref "J3") (pin "332") (pinfunction "332_332") (pintype "passive"))
    )
    (net (code "205") (name "unconnected-(J3-Pad333)") (class "Default")
      (node (ref "J3") (pin "333") (pinfunction "333_333") (pintype "passive"))
    )
    (net (code "206") (name "unconnected-(J3-Pad335)") (class "Default")
      (node (ref "J3") (pin "335") (pinfunction "335_335") (pintype "passive"))
    )
    (net (code "207") (name "unconnected-(J3-Pad336)") (class "Default")
      (node (ref "J3") (pin "336") (pinfunction "336_336") (pintype "passive"))
    )
    (net (code "208") (name "unconnected-(J3-Pad338)") (class "Default")
      (node (ref "J3") (pin "338") (pinfunction "338_338") (pintype "passive"))
    )
    (net (code "209") (name "unconnected-(J3-Pad339)") (class "Default")
      (node (ref "J3") (pin "339") (pinfunction "339_339") (pintype "passive"))
    )
    (net (code "210") (name "unconnected-(J3-Pad342)") (class "Default")
      (node (ref "J3") (pin "342") (pinfunction "342_342") (pintype "passive"))
    )
    (net (code "211") (name "unconnected-(J3-Pad343)") (class "Default")
      (node (ref "J3") (pin "343") (pinfunction "343_343") (pintype "passive"))
    )
    (net (code "212") (name "unconnected-(J3-Pad345)") (class "Default")
      (node (ref "J3") (pin "345") (pinfunction "345_345") (pintype "passive"))
    )
    (net (code "213") (name "unconnected-(J3-Pad346)") (class "Default")
      (node (ref "J3") (pin "346") (pinfunction "346_346") (pintype "passive"))
    )
    (net (code "214") (name "unconnected-(J3-Pad348)") (class "Default")
      (node (ref "J3") (pin "348") (pinfunction "348_348") (pintype "passive"))
    )
    (net (code "215") (name "unconnected-(J3-Pad349)") (class "Default")
      (node (ref "J3") (pin "349") (pinfunction "349_349") (pintype "passive"))
    )
    (net (code "216") (name "unconnected-(J3-Pad352)") (class "Default")
      (node (ref "J3") (pin "352") (pinfunction "352_352") (pintype "passive"))
    )
    (net (code "217") (name "unconnected-(J3-Pad353)") (class "Default")
      (node (ref "J3") (pin "353") (pinfunction "353_353") (pintype "passive"))
    )
    (net (code "218") (name "unconnected-(J3-Pad355)") (class "Default")
      (node (ref "J3") (pin "355") (pinfunction "355_355") (pintype "passive"))
    )
    (net (code "219") (name "unconnected-(J3-Pad356)") (class "Default")
      (node (ref "J3") (pin "356") (pinfunction "356_356") (pintype "passive"))
    )
    (net (code "220") (name "unconnected-(J3-Pad358)") (class "Default")
      (node (ref "J3") (pin "358") (pinfunction "358_358") (pintype "passive"))
    )
    (net (code "221") (name "unconnected-(J3-Pad359)") (class "Default")
      (node (ref "J3") (pin "359") (pinfunction "359_359") (pintype "passive"))
    )
    (net (code "222") (name "unconnected-(J3-Pad362)") (class "Default")
      (node (ref "J3") (pin "362") (pinfunction "362_362") (pintype "passive"))
    )
    (net (code "223") (name "unconnected-(J3-Pad363)") (class "Default")
      (node (ref "J3") (pin "363") (pinfunction "363_363") (pintype "passive"))
    )
    (net (code "224") (name "unconnected-(J3-Pad365)") (class "Default")
      (node (ref "J3") (pin "365") (pinfunction "365_365") (pintype "passive"))
    )
    (net (code "225") (name "unconnected-(J3-Pad366)") (class "Default")
      (node (ref "J3") (pin "366") (pinfunction "366_366") (pintype "passive"))
    )
    (net (code "226") (name "unconnected-(J3-Pad368)") (class "Default")
      (node (ref "J3") (pin "368") (pinfunction "368_368") (pintype "passive"))
    )
    (net (code "227") (name "unconnected-(J3-Pad369)") (class "Default")
      (node (ref "J3") (pin "369") (pinfunction "369_369") (pintype "passive"))
    )
    (net (code "228") (name "unconnected-(J3-Pad372)") (class "Default")
      (node (ref "J3") (pin "372") (pinfunction "372_372") (pintype "passive"))
    )
    (net (code "229") (name "unconnected-(J3-Pad373)") (class "Default")
      (node (ref "J3") (pin "373") (pinfunction "373_373") (pintype "passive"))
    )
    (net (code "230") (name "unconnected-(J3-Pad375)") (class "Default")
      (node (ref "J3") (pin "375") (pinfunction "375_375") (pintype "passive"))
    )
    (net (code "231") (name "unconnected-(J3-Pad376)") (class "Default")
      (node (ref "J3") (pin "376") (pinfunction "376_376") (pintype "passive"))
    )
    (net (code "232") (name "unconnected-(J3-Pad378)") (class "Default")
      (node (ref "J3") (pin "378") (pinfunction "378_378") (pintype "passive"))
    )
    (net (code "233") (name "unconnected-(J3-Pad379)") (class "Default")
      (node (ref "J3") (pin "379") (pinfunction "379_379") (pintype "passive"))
    )
    (net (code "234") (name "unconnected-(J3-Pad382)") (class "Default")
      (node (ref "J3") (pin "382") (pinfunction "382_382") (pintype "passive"))
    )
    (net (code "235") (name "unconnected-(J3-Pad383)") (class "Default")
      (node (ref "J3") (pin "383") (pinfunction "383_383") (pintype "passive"))
    )
    (net (code "236") (name "unconnected-(J3-Pad385)") (class "Default")
      (node (ref "J3") (pin "385") (pinfunction "385_385") (pintype "passive"))
    )
    (net (code "237") (name "unconnected-(J3-Pad386)") (class "Default")
      (node (ref "J3") (pin "386") (pinfunction "386_386") (pintype "passive"))
    )
    (net (code "238") (name "unconnected-(J3-Pad388)") (class "Default")
      (node (ref "J3") (pin "388") (pinfunction "388_388") (pintype "passive"))
    )
    (net (code "239") (name "unconnected-(J3-Pad389)") (class "Default")
      (node (ref "J3") (pin "389") (pinfunction "389_389") (pintype "passive"))
    )
    (net (code "240") (name "unconnected-(J3-Pad392)") (class "Default")
      (node (ref "J3") (pin "392") (pinfunction "392_392") (pintype "passive"))
    )
    (net (code "241") (name "unconnected-(J3-Pad393)") (class "Default")
      (node (ref "J3") (pin "393") (pinfunction "393_393") (pintype "passive"))
    )
    (net (code "242") (name "unconnected-(J3-Pad395)") (class "Default")
      (node (ref "J3") (pin "395") (pinfunction "395_395") (pintype "passive"))
    )
    (net (code "243") (name "unconnected-(J3-Pad396)") (class "Default")
      (node (ref "J3") (pin "396") (pinfunction "396_396") (pintype "passive"))
    )
    (net (code "244") (name "unconnected-(J3-Pad398)") (class "Default")
      (node (ref "J3") (pin "398") (pinfunction "398_398") (pintype "passive"))
    )
    (net (code "245") (name "unconnected-(J3-Pad399)") (class "Default")
      (node (ref "J3") (pin "399") (pinfunction "399_399") (pintype "passive"))
    )
  )
)
